# HVP_ADC_CONNECTIONS.net
KiCad netlist of a schematic drawn in Altium Designer
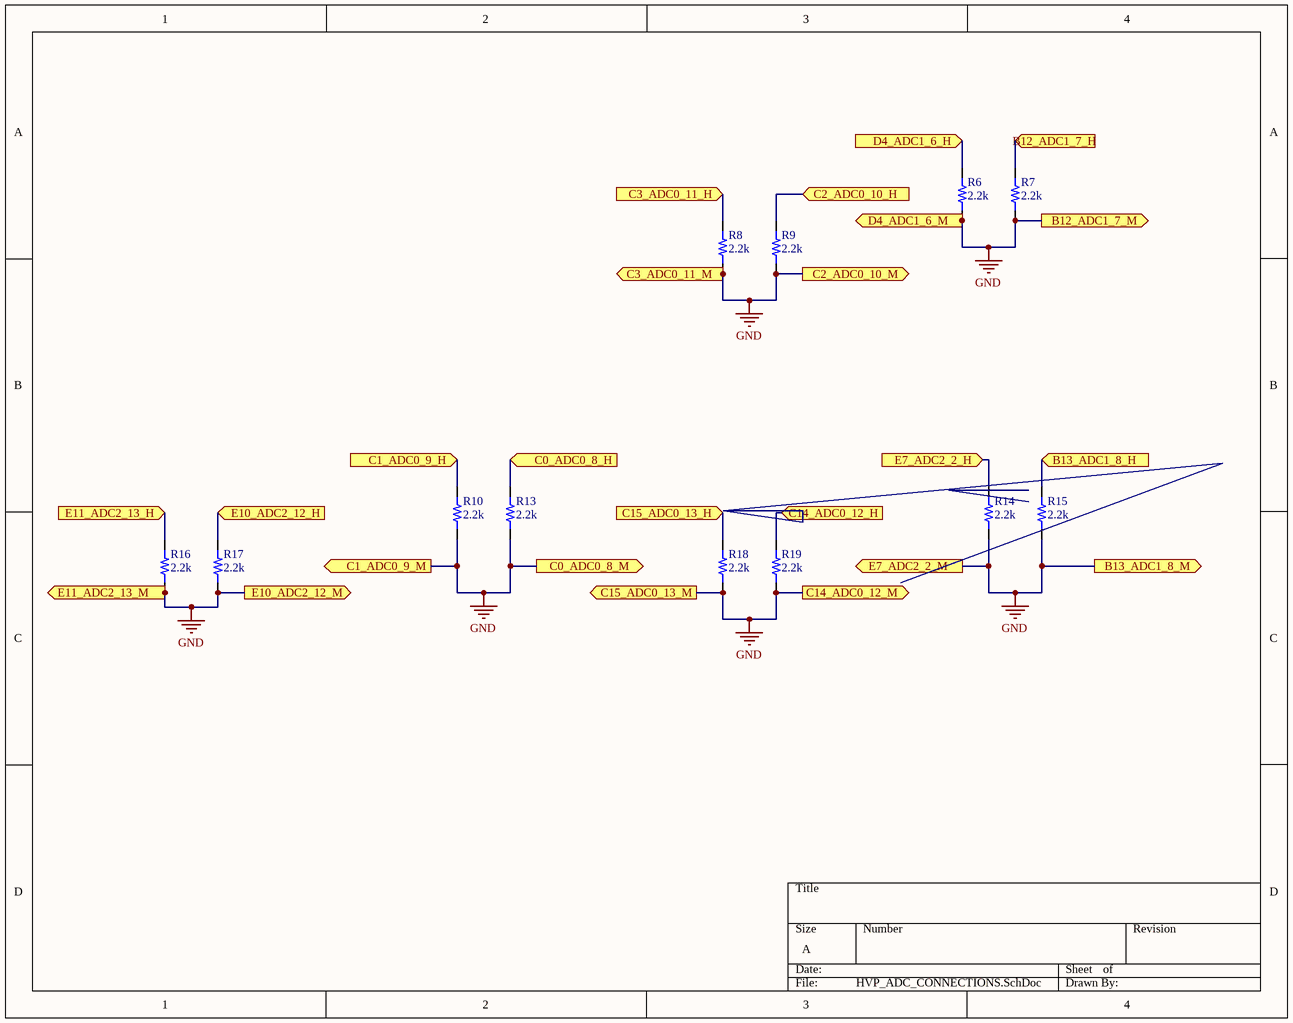
[diagram p0: HVP_ADC_CONNECTIONS.SchDoc]

(export (version "E")
  (design (tool "Eeschema 10.0.6"))
  (components
    (comp (ref "R6")
      (value "2.2k")
      (footprint "RES 0402/1005")
      (fields
        (field (name "TOLERANCE") "1%")
        (field (name "POWER") "1/10W")
        (field (name "Comment") "Resistor 2.2k 0402 1/10W 1%")
        (field (name "CREATED_BY") "Nick Mah")
      )
      (libsource (lib "Altium-Lib") (part "Resistor"))
    )
    (comp (ref "R7")
      (value "2.2k")
      (footprint "RES 0402/1005")
      (fields
        (field (name "TOLERANCE") "1%")
        (field (name "POWER") "1/10W")
        (field (name "Comment") "Resistor 2.2k 0402 1/10W 1%")
        (field (name "CREATED_BY") "Nick Mah")
      )
      (libsource (lib "Altium-Lib") (part "Resistor"))
    )
    (comp (ref "R8")
      (value "2.2k")
      (footprint "RES 0402/1005")
      (fields
        (field (name "TOLERANCE") "1%")
        (field (name "POWER") "1/10W")
        (field (name "Comment") "Resistor 2.2k 0402 1/10W 1%")
        (field (name "CREATED_BY") "Nick Mah")
      )
      (libsource (lib "Altium-Lib") (part "Resistor"))
    )
    (comp (ref "R9")
      (value "2.2k")
      (footprint "RES 0402/1005")
      (fields
        (field (name "TOLERANCE") "1%")
        (field (name "POWER") "1/10W")
        (field (name "Comment") "Resistor 2.2k 0402 1/10W 1%")
        (field (name "CREATED_BY") "Nick Mah")
      )
      (libsource (lib "Altium-Lib") (part "Resistor"))
    )
    (comp (ref "R10")
      (value "2.2k")
      (footprint "RES 0402/1005")
      (fields
        (field (name "TOLERANCE") "1%")
        (field (name "POWER") "1/10W")
        (field (name "Comment") "Resistor 2.2k 0402 1/10W 1%")
        (field (name "CREATED_BY") "Nick Mah")
      )
      (libsource (lib "Altium-Lib") (part "Resistor"))
    )
    (comp (ref "R13")
      (value "2.2k")
      (footprint "RES 0402/1005")
      (fields
        (field (name "TOLERANCE") "1%")
        (field (name "POWER") "1/10W")
        (field (name "Comment") "Resistor 2.2k 0402 1/10W 1%")
        (field (name "CREATED_BY") "Nick Mah")
      )
      (libsource (lib "Altium-Lib") (part "Resistor"))
    )
    (comp (ref "R14")
      (value "2.2k")
      (footprint "RES 0402/1005")
      (fields
        (field (name "TOLERANCE") "1%")
        (field (name "POWER") "1/10W")
        (field (name "Comment") "Resistor 2.2k 0402 1/10W 1%")
        (field (name "CREATED_BY") "Nick Mah")
      )
      (libsource (lib "Altium-Lib") (part "Resistor"))
    )
    (comp (ref "R15")
      (value "2.2k")
      (footprint "RES 0402/1005")
      (fields
        (field (name "TOLERANCE") "1%")
        (field (name "POWER") "1/10W")
        (field (name "Comment") "Resistor 2.2k 0402 1/10W 1%")
        (field (name "CREATED_BY") "Nick Mah")
      )
      (libsource (lib "Altium-Lib") (part "Resistor"))
    )
    (comp (ref "R16")
      (value "2.2k")
      (footprint "RES 0402/1005")
      (fields
        (field (name "TOLERANCE") "1%")
        (field (name "POWER") "1/10W")
        (field (name "Comment") "Resistor 2.2k 0402 1/10W 1%")
        (field (name "CREATED_BY") "Nick Mah")
      )
      (libsource (lib "Altium-Lib") (part "Resistor"))
    )
    (comp (ref "R17")
      (value "2.2k")
      (footprint "RES 0402/1005")
      (fields
        (field (name "TOLERANCE") "1%")
        (field (name "POWER") "1/10W")
        (field (name "Comment") "Resistor 2.2k 0402 1/10W 1%")
        (field (name "CREATED_BY") "Nick Mah")
      )
      (libsource (lib "Altium-Lib") (part "Resistor"))
    )
    (comp (ref "R18")
      (value "2.2k")
      (footprint "RES 0402/1005")
      (fields
        (field (name "TOLERANCE") "1%")
        (field (name "POWER") "1/10W")
        (field (name "Comment") "Resistor 2.2k 0402 1/10W 1%")
        (field (name "CREATED_BY") "Nick Mah")
      )
      (libsource (lib "Altium-Lib") (part "Resistor"))
    )
    (comp (ref "R19")
      (value "2.2k")
      (footprint "RES 0402/1005")
      (fields
        (field (name "TOLERANCE") "1%")
        (field (name "POWER") "1/10W")
        (field (name "Comment") "Resistor 2.2k 0402 1/10W 1%")
        (field (name "CREATED_BY") "Nick Mah")
      )
      (libsource (lib "Altium-Lib") (part "Resistor"))
    )
  )
  (nets
    (net (code "1") (name "/B12_ADC1_7_H") (class "Default")
      (node (ref "R7") (pin "2") (pinfunction "2_2") (pintype "passive"))
    )
    (net (code "2") (name "/B13_ADC1_8_H") (class "Default")
      (node (ref "R15") (pin "2") (pinfunction "2_2") (pintype "passive"))
    )
    (net (code "3") (name "/C0_ADC0_8_H") (class "Default")
      (node (ref "R13") (pin "2") (pinfunction "2_2") (pintype "passive"))
    )
    (net (code "4") (name "/C1_ADC0_9_H") (class "Default")
      (node (ref "R10") (pin "2") (pinfunction "2_2") (pintype "passive"))
    )
    (net (code "5") (name "/C2_ADC0_10_H") (class "Default")
      (node (ref "R9") (pin "2") (pinfunction "2_2") (pintype "passive"))
    )
    (net (code "6") (name "/C3_ADC0_11_H") (class "Default")
      (node (ref "R8") (pin "2") (pinfunction "2_2") (pintype "passive"))
    )
    (net (code "7") (name "/C14_ADC0_12_H") (class "Default")
      (node (ref "R19") (pin "2") (pinfunction "2_2") (pintype "passive"))
    )
    (net (code "8") (name "/C15_ADC0_13_H") (class "Default")
      (node (ref "R18") (pin "2") (pinfunction "2_2") (pintype "passive"))
    )
    (net (code "9") (name "/D4_ADC1_6_H") (class "Default")
      (node (ref "R6") (pin "2") (pinfunction "2_2") (pintype "passive"))
    )
    (net (code "10") (name "/E7_ADC2_2_H") (class "Default")
      (node (ref "R14") (pin "2") (pinfunction "2_2") (pintype "passive"))
    )
    (net (code "11") (name "/E10_ADC2_12_H") (class "Default")
      (node (ref "R17") (pin "2") (pinfunction "2_2") (pintype "passive"))
    )
    (net (code "12") (name "/E11_ADC2_13_H") (class "Default")
      (node (ref "R16") (pin "2") (pinfunction "2_2") (pintype "passive"))
    )
    (net (code "13") (name "GND") (class "Default")
      (node (ref "R10") (pin "1") (pinfunction "1_1") (pintype "passive"))
      (node (ref "R13") (pin "1") (pinfunction "1_1") (pintype "passive"))
      (node (ref "R14") (pin "1") (pinfunction "1_1") (pintype "passive"))
      (node (ref "R15") (pin "1") (pinfunction "1_1") (pintype "passive"))
      (node (ref "R16") (pin "1") (pinfunction "1_1") (pintype "passive"))
      (node (ref "R17") (pin "1") (pinfunction "1_1") (pintype "passive"))
      (node (ref "R18") (pin "1") (pinfunction "1_1") (pintype "passive"))
      (node (ref "R19") (pin "1") (pinfunction "1_1") (pintype "passive"))
      (node (ref "R6") (pin "1") (pinfunction "1_1") (pintype "passive"))
      (node (ref "R7") (pin "1") (pinfunction "1_1") (pintype "passive"))
      (node (ref "R8") (pin "1") (pinfunction "1_1") (pintype "passive"))
      (node (ref "R9") (pin "1") (pinfunction "1_1") (pintype "passive"))
    )
  )
)
